# Loginator_1_1.net
KiCad netlist of a schematic drawn in EAGLE
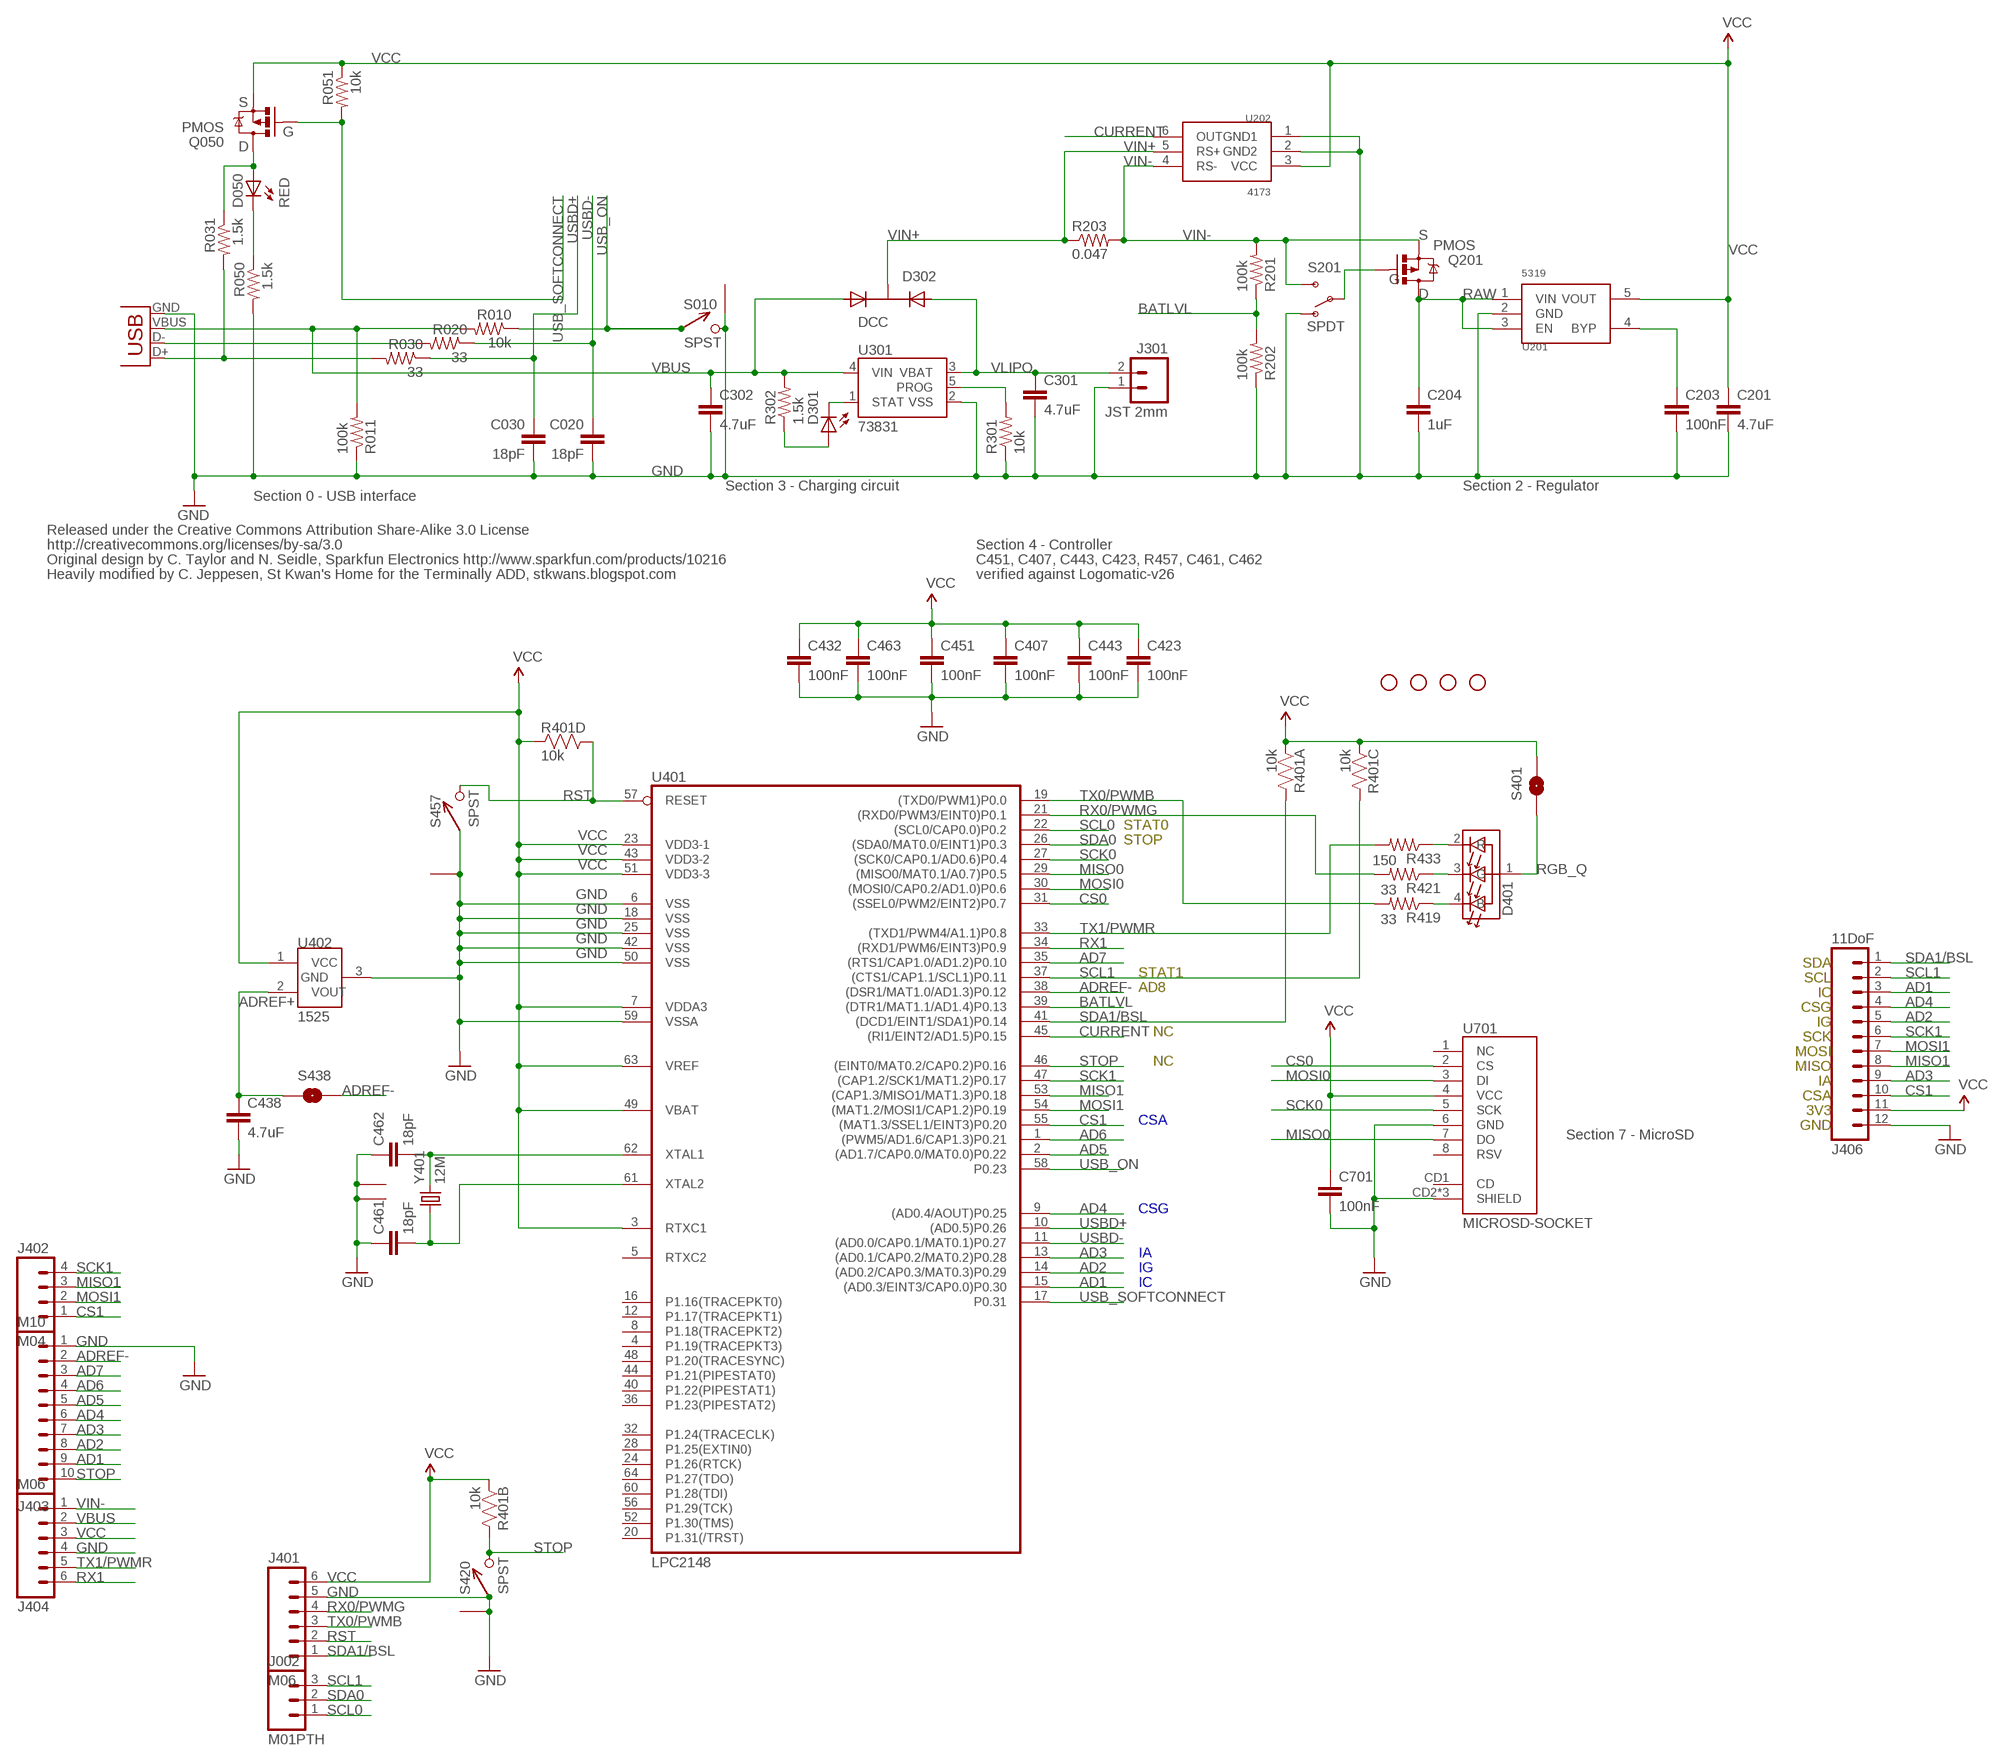
[diagram p0: schematic, sheet 1]

(export (version "E")
  (design (tool "Eeschema 10.0.6"))
  (components
    (comp (ref "C020")
      (value "18pF")
      (footprint "eagle-import:0402-CAP")
      (libsource (lib "eagle-import") (part "CAP0402-CAP"))
    )
    (comp (ref "C030")
      (value "18pF")
      (footprint "eagle-import:0402-CAP")
      (libsource (lib "eagle-import") (part "CAP0402-CAP"))
    )
    (comp (ref "C201")
      (value "4.7uF")
      (footprint "eagle-import:0402-CAP")
      (libsource (lib "eagle-import") (part "CAP0402-CAP"))
    )
    (comp (ref "C203")
      (value "100nF")
      (footprint "eagle-import:0402-CAP")
      (libsource (lib "eagle-import") (part "CAP0402-CAP"))
    )
    (comp (ref "C204")
      (value "1uF")
      (footprint "eagle-import:0402-CAP")
      (libsource (lib "eagle-import") (part "CAP0402-CAP"))
    )
    (comp (ref "C301")
      (value "4.7uF")
      (footprint "eagle-import:0402-CAP")
      (libsource (lib "eagle-import") (part "CAP0402-CAP"))
    )
    (comp (ref "C302")
      (value "4.7uF")
      (footprint "eagle-import:0402-CAP")
      (libsource (lib "eagle-import") (part "CAP0402-CAP"))
    )
    (comp (ref "C407")
      (value "100nF")
      (footprint "eagle-import:0402-CAP")
      (libsource (lib "eagle-import") (part "CAP0402-CAP"))
    )
    (comp (ref "C423")
      (value "100nF")
      (footprint "eagle-import:0402-CAP")
      (libsource (lib "eagle-import") (part "CAP0402-CAP"))
    )
    (comp (ref "C432")
      (value "100nF")
      (footprint "eagle-import:0402-CAP")
      (libsource (lib "eagle-import") (part "CAP0402-CAP"))
    )
    (comp (ref "C438")
      (value "4.7uF")
      (footprint "eagle-import:0402-CAP")
      (libsource (lib "eagle-import") (part "CAP0402-CAP"))
    )
    (comp (ref "C443")
      (value "100nF")
      (footprint "eagle-import:0402-CAP")
      (libsource (lib "eagle-import") (part "CAP0402-CAP"))
    )
    (comp (ref "C451")
      (value "100nF")
      (footprint "eagle-import:0402-CAP")
      (libsource (lib "eagle-import") (part "CAP0402-CAP"))
    )
    (comp (ref "C461")
      (value "18pF")
      (footprint "eagle-import:0402-CAP")
      (libsource (lib "eagle-import") (part "CAP0402-CAP"))
    )
    (comp (ref "C462")
      (value "18pF")
      (footprint "eagle-import:0402-CAP")
      (libsource (lib "eagle-import") (part "CAP0402-CAP"))
    )
    (comp (ref "C463")
      (value "100nF")
      (footprint "eagle-import:0402-CAP")
      (libsource (lib "eagle-import") (part "CAP0402-CAP"))
    )
    (comp (ref "C701")
      (value "100nF")
      (footprint "eagle-import:0402-CAP")
      (libsource (lib "eagle-import") (part "CAP0402-CAP"))
    )
    (comp (ref "D050")
      (value "RED")
      (footprint "eagle-import:LED-0603")
      (libsource (lib "eagle-import") (part "LED0603"))
    )
    (comp (ref "D301")
      (value "RED")
      (footprint "eagle-import:LED-0603")
      (libsource (lib "eagle-import") (part "LED0603"))
    )
    (comp (ref "D302")
      (value "DCC")
      (footprint "eagle-import:SOT-23-3")
      (libsource (lib "eagle-import") (part "PMEG2005CT"))
    )
    (comp (ref "D401")
      (value "HSMF-C118")
      (footprint "eagle-import:HSMF-C118")
      (libsource (lib "eagle-import") (part "HSMF-C118"))
    )
    (comp (ref "J001")
      (value "USBSMD")
      (footprint "eagle-import:USB-MINIB")
      (libsource (lib "eagle-import") (part "USBSMD"))
    )
    (comp (ref "J002")
      (value "M01PTH")
      (footprint "eagle-import:1X03")
      (libsource (lib "eagle-import") (part "M03PTH"))
    )
    (comp (ref "J301")
      (value "JST 2mm")
      (footprint "eagle-import:JST-2-SMD")
      (libsource (lib "eagle-import") (part "M02-JST-2MM-SMT"))
    )
    (comp (ref "J401")
      (value "M06")
      (footprint "eagle-import:1X06")
      (libsource (lib "eagle-import") (part "M06SIP"))
    )
    (comp (ref "J402")
      (value "M04")
      (footprint "eagle-import:1X04")
      (libsource (lib "eagle-import") (part "M04PTH"))
    )
    (comp (ref "J403")
      (value "M10")
      (footprint "eagle-import:1X10")
      (libsource (lib "eagle-import") (part "M10{dblquote}"))
    )
    (comp (ref "J404")
      (value "M06")
      (footprint "eagle-import:1X06")
      (libsource (lib "eagle-import") (part "M06SIP"))
    )
    (comp (ref "J406")
      (value "11DoF")
      (footprint "eagle-import:1X12")
      (libsource (lib "eagle-import") (part "M12PTH"))
    )
    (comp (ref "JP1")
      (value "STAND-OFF")
      (footprint "eagle-import:STAND-OFF")
      (libsource (lib "eagle-import") (part "STAND-OFF"))
    )
    (comp (ref "JP2")
      (value "STAND-OFF")
      (footprint "eagle-import:STAND-OFF")
      (libsource (lib "eagle-import") (part "STAND-OFF"))
    )
    (comp (ref "JP3")
      (value "STAND-OFF")
      (footprint "eagle-import:STAND-OFF")
      (libsource (lib "eagle-import") (part "STAND-OFF"))
    )
    (comp (ref "JP4")
      (value "STAND-OFF")
      (footprint "eagle-import:STAND-OFF")
      (libsource (lib "eagle-import") (part "STAND-OFF"))
    )
    (comp (ref "Q050")
      (value "PMOS")
      (footprint "eagle-import:SOT23-3")
      (libsource (lib "eagle-import") (part "MOSFET-PCHANNELSMD"))
    )
    (comp (ref "Q201")
      (value "PMOS")
      (footprint "eagle-import:SOT23-3")
      (libsource (lib "eagle-import") (part "MOSFET-PCHANNELSMD"))
    )
    (comp (ref "R010")
      (value "10k")
      (footprint "eagle-import:0402-RES")
      (libsource (lib "eagle-import") (part "RESISTOR0402-RES"))
    )
    (comp (ref "R011")
      (value "100k")
      (footprint "eagle-import:0402-RES")
      (libsource (lib "eagle-import") (part "RESISTOR0402-RES"))
    )
    (comp (ref "R020")
      (value "33")
      (footprint "eagle-import:0402-RES")
      (libsource (lib "eagle-import") (part "RESISTOR0402-RES"))
    )
    (comp (ref "R030")
      (value "33")
      (footprint "eagle-import:0402-RES")
      (libsource (lib "eagle-import") (part "RESISTOR0402-RES"))
    )
    (comp (ref "R031")
      (value "1.5k")
      (footprint "eagle-import:0402-RES")
      (libsource (lib "eagle-import") (part "RESISTOR0402-RES"))
    )
    (comp (ref "R050")
      (value "1.5k")
      (footprint "eagle-import:0402-RES")
      (libsource (lib "eagle-import") (part "RESISTOR0402-RES"))
    )
    (comp (ref "R051")
      (value "10k")
      (footprint "eagle-import:0402-RES")
      (libsource (lib "eagle-import") (part "RESISTOR0402-RES"))
    )
    (comp (ref "R201")
      (value "100k")
      (footprint "eagle-import:0402-RES")
      (libsource (lib "eagle-import") (part "RESISTOR0402-RES"))
    )
    (comp (ref "R202")
      (value "100k")
      (footprint "eagle-import:0402-RES")
      (libsource (lib "eagle-import") (part "RESISTOR0402-RES"))
    )
    (comp (ref "R203")
      (value "0.047")
      (footprint "eagle-import:0402-RES")
      (libsource (lib "eagle-import") (part "RESISTOR0402-RES"))
    )
    (comp (ref "R301")
      (value "10k")
      (footprint "eagle-import:0402-RES")
      (libsource (lib "eagle-import") (part "RESISTOR0402-RES"))
    )
    (comp (ref "R302")
      (value "1.5k")
      (footprint "eagle-import:0402-RES")
      (libsource (lib "eagle-import") (part "RESISTOR0402-RES"))
    )
    (comp (ref "R401")
      (value "10k")
      (footprint "eagle-import:CRA04")
      (libsource (lib "eagle-import") (part "RP404"))
    )
    (comp (ref "R419")
      (value "33")
      (footprint "eagle-import:0402-RES")
      (libsource (lib "eagle-import") (part "RESISTOR0402-RES"))
    )
    (comp (ref "R421")
      (value "33")
      (footprint "eagle-import:0402-RES")
      (libsource (lib "eagle-import") (part "RESISTOR0402-RES"))
    )
    (comp (ref "R433")
      (value "150")
      (footprint "eagle-import:0402-RES")
      (libsource (lib "eagle-import") (part "RESISTOR0402-RES"))
    )
    (comp (ref "S010")
      (value "SPST")
      (footprint "eagle-import:B3U-1100P")
      (libsource (lib "eagle-import") (part "B3U-1100P"))
    )
    (comp (ref "S201")
      (value "SPDT")
      (footprint "eagle-import:AYZ0202")
      (libsource (lib "eagle-import") (part "SWITCH-SPSTSMD"))
    )
    (comp (ref "S401")
      (value "SOLDERJUMPERNO")
      (footprint "eagle-import:SJ_2S-NO")
      (libsource (lib "eagle-import") (part "SOLDERJUMPERNO"))
    )
    (comp (ref "S420")
      (value "SPST")
      (footprint "eagle-import:B3U-1100P")
      (libsource (lib "eagle-import") (part "B3U-1100P"))
    )
    (comp (ref "S438")
      (value "SOLDERJUMPERNO")
      (footprint "eagle-import:SJ_2S-NO")
      (libsource (lib "eagle-import") (part "SOLDERJUMPERNO"))
    )
    (comp (ref "S457")
      (value "SPST")
      (footprint "eagle-import:B3U-1100P")
      (libsource (lib "eagle-import") (part "B3U-1100P"))
    )
    (comp (ref "U201")
      (value "5319")
      (footprint "eagle-import:SOT-23-5")
      (libsource (lib "eagle-import") (part "MIC5319D5"))
    )
    (comp (ref "U202")
      (value "4173")
      (footprint "eagle-import:SOT-23-6")
      (libsource (lib "eagle-import") (part "MAX4173"))
    )
    (comp (ref "U301")
      (value "73831")
      (footprint "eagle-import:SOT23-5")
      (libsource (lib "eagle-import") (part "MCP73831"))
    )
    (comp (ref "U401")
      (value "LPC2148")
      (footprint "eagle-import:SQFP-S-10X10-64")
      (libsource (lib "eagle-import") (part "LPC213X"))
    )
    (comp (ref "U402")
      (value "1525")
      (footprint "eagle-import:SOT-23-3")
      (libsource (lib "eagle-import") (part "MCP1525"))
    )
    (comp (ref "U701")
      (value "MICROSD-SOCKET")
      (footprint "eagle-import:MICROSD-SOCKET-PP")
      (libsource (lib "eagle-import") (part "MICROSD-SOCKET"))
    )
    (comp (ref "Y401")
      (value "12M")
      (footprint "eagle-import:CRYSTAL_SMD")
      (libsource (lib "eagle-import") (part "TSX-3225"))
    )
  )
  (nets
    (net (code "1") (name "/AD1") (class "Default")
      (node (ref "J403") (pin "9") (pinfunction "9_9") (pintype "passive"))
      (node (ref "J406") (pin "3") (pinfunction "3_3") (pintype "passive"))
      (node (ref "U401") (pin "15") (pinfunction "(AD0.3/EINT3/CAP0.0)P0.30_15") (pintype "bidirectional"))
    )
    (net (code "2") (name "/AD2") (class "Default")
      (node (ref "J403") (pin "8") (pinfunction "8_8") (pintype "passive"))
      (node (ref "J406") (pin "5") (pinfunction "5_5") (pintype "passive"))
      (node (ref "U401") (pin "14") (pinfunction "(AD0.2/CAP0.3/MAT0.3)P0.29_14") (pintype "bidirectional"))
    )
    (net (code "3") (name "/AD3") (class "Default")
      (node (ref "J403") (pin "7") (pinfunction "7_7") (pintype "passive"))
      (node (ref "J406") (pin "9") (pinfunction "9_9") (pintype "passive"))
      (node (ref "U401") (pin "13") (pinfunction "(AD0.1/CAP0.2/MAT0.2)P0.28_13") (pintype "bidirectional"))
    )
    (net (code "4") (name "/AD4") (class "Default")
      (node (ref "J403") (pin "6") (pinfunction "6_6") (pintype "passive"))
      (node (ref "J406") (pin "4") (pinfunction "4_4") (pintype "passive"))
      (node (ref "U401") (pin "9") (pinfunction "(AD0.4/AOUT)P0.25_9") (pintype "bidirectional"))
    )
    (net (code "5") (name "/AD5") (class "Default")
      (node (ref "J403") (pin "5") (pinfunction "5_5") (pintype "passive"))
      (node (ref "U401") (pin "2") (pinfunction "(AD1.7/CAP0.0/MAT0.0)P0.22_2") (pintype "bidirectional"))
    )
    (net (code "6") (name "/AD6") (class "Default")
      (node (ref "J403") (pin "4") (pinfunction "4_4") (pintype "passive"))
      (node (ref "U401") (pin "1") (pinfunction "(PWM5/AD1.6/CAP1.3)P0.21_1") (pintype "bidirectional"))
    )
    (net (code "7") (name "/AD7") (class "Default")
      (node (ref "J403") (pin "3") (pinfunction "3_3") (pintype "passive"))
      (node (ref "U401") (pin "35") (pinfunction "(RTS1/CAP1.0/AD1.2)P0.10_35") (pintype "bidirectional"))
    )
    (net (code "8") (name "/ADREF+") (class "Default")
      (node (ref "C438") (pin "1") (pinfunction "1_1") (pintype "passive"))
      (node (ref "S438") (pin "1") (pinfunction "1_1") (pintype "passive"))
      (node (ref "U402") (pin "2") (pinfunction "VOUT_2") (pintype "bidirectional"))
    )
    (net (code "9") (name "/ADREF-") (class "Default")
      (node (ref "J403") (pin "2") (pinfunction "2_2") (pintype "passive"))
      (node (ref "S438") (pin "2") (pinfunction "2_2") (pintype "passive"))
      (node (ref "U401") (pin "38") (pinfunction "(DSR1/MAT1.0/AD1.3)P0.12_38") (pintype "bidirectional"))
    )
    (net (code "10") (name "/BATLVL") (class "Default")
      (node (ref "R201") (pin "1") (pinfunction "1_1") (pintype "passive"))
      (node (ref "R202") (pin "2") (pinfunction "2_2") (pintype "passive"))
      (node (ref "U401") (pin "39") (pinfunction "(DTR1/MAT1.1/AD1.4)P0.13_39") (pintype "bidirectional"))
    )
    (net (code "11") (name "/CS0") (class "Default")
      (node (ref "U401") (pin "31") (pinfunction "(SSEL0/PWM2/EINT2)P0.7_31") (pintype "bidirectional"))
      (node (ref "U701") (pin "2") (pinfunction "CS_2") (pintype "bidirectional"))
    )
    (net (code "12") (name "/CS1") (class "Default")
      (node (ref "J402") (pin "1") (pinfunction "1_1") (pintype "passive"))
      (node (ref "J406") (pin "10") (pinfunction "10_10") (pintype "passive"))
      (node (ref "U401") (pin "55") (pinfunction "(MAT1.3/SSEL1/EINT3)P0.20_55") (pintype "bidirectional"))
    )
    (net (code "13") (name "/CURRENT") (class "Default")
      (node (ref "U202") (pin "6") (pinfunction "OUT_6") (pintype "bidirectional"))
      (node (ref "U401") (pin "45") (pinfunction "(RI1/EINT2/AD1.5)P0.15_45") (pintype "bidirectional"))
    )
    (net (code "14") (name "/MISO0") (class "Default")
      (node (ref "U401") (pin "29") (pinfunction "(MISO0/MAT0.1/A0.7)P0.5_29") (pintype "bidirectional"))
      (node (ref "U701") (pin "7") (pinfunction "DO_7") (pintype "bidirectional"))
    )
    (net (code "15") (name "/MISO1") (class "Default")
      (node (ref "J402") (pin "3") (pinfunction "3_3") (pintype "passive"))
      (node (ref "J406") (pin "8") (pinfunction "8_8") (pintype "passive"))
      (node (ref "U401") (pin "53") (pinfunction "(CAP1.3/MISO1/MAT1.3)P0.18_53") (pintype "bidirectional"))
    )
    (net (code "16") (name "/MOSI0") (class "Default")
      (node (ref "U401") (pin "30") (pinfunction "(MOSI0/CAP0.2/AD1.0)P0.6_30") (pintype "bidirectional"))
      (node (ref "U701") (pin "3") (pinfunction "DI_3") (pintype "bidirectional"))
    )
    (net (code "17") (name "/MOSI1") (class "Default")
      (node (ref "J402") (pin "2") (pinfunction "2_2") (pintype "passive"))
      (node (ref "J406") (pin "7") (pinfunction "7_7") (pintype "passive"))
      (node (ref "U401") (pin "54") (pinfunction "(MAT1.2/MOSI1/CAP1.2)P0.19_54") (pintype "bidirectional"))
    )
    (net (code "18") (name "/RAW") (class "Default")
      (node (ref "C204") (pin "1") (pinfunction "1_1") (pintype "passive"))
      (node (ref "Q201") (pin "3") (pinfunction "D_3") (pintype "passive"))
      (node (ref "U201") (pin "1") (pinfunction "VIN_1") (pintype "bidirectional"))
      (node (ref "U201") (pin "3") (pinfunction "EN_3") (pintype "bidirectional"))
    )
    (net (code "19") (name "/RGB_Q") (class "Default")
      (node (ref "D401") (pin "1") (pinfunction "A_1") (pintype "passive"))
      (node (ref "S401") (pin "1") (pinfunction "1_1") (pintype "passive"))
    )
    (net (code "20") (name "/RST") (class "Default")
      (node (ref "J401") (pin "2") (pinfunction "2_2") (pintype "passive"))
      (node (ref "R401") (pin "5") (pinfunction "2_5") (pintype "passive"))
      (node (ref "S457") (pin "P$2") (pinfunction "2_P$2") (pintype "bidirectional"))
      (node (ref "U401") (pin "57") (pinfunction "RESET_57") (pintype "input"))
    )
    (net (code "21") (name "/RX0{slash}PWMG") (class "Default")
      (node (ref "J401") (pin "4") (pinfunction "4_4") (pintype "passive"))
      (node (ref "R421") (pin "2") (pinfunction "2_2") (pintype "passive"))
      (node (ref "U401") (pin "21") (pinfunction "(RXD0/PWM3/EINT0)P0.1_21") (pintype "bidirectional"))
    )
    (net (code "22") (name "/RX1") (class "Default")
      (node (ref "J404") (pin "6") (pinfunction "6_6") (pintype "passive"))
      (node (ref "U401") (pin "34") (pinfunction "(RXD1/PWM6/EINT3)P0.9_34") (pintype "bidirectional"))
    )
    (net (code "23") (name "/SCK0") (class "Default")
      (node (ref "U401") (pin "27") (pinfunction "(SCK0/CAP0.1/AD0.6)P0.4_27") (pintype "bidirectional"))
      (node (ref "U701") (pin "5") (pinfunction "SCK_5") (pintype "bidirectional"))
    )
    (net (code "24") (name "/SCK1") (class "Default")
      (node (ref "J402") (pin "4") (pinfunction "4_4") (pintype "passive"))
      (node (ref "J406") (pin "6") (pinfunction "6_6") (pintype "passive"))
      (node (ref "U401") (pin "47") (pinfunction "(CAP1.2/SCK1/MAT1.2)P0.17_47") (pintype "bidirectional"))
    )
    (net (code "25") (name "/SCL0") (class "Default")
      (node (ref "J002") (pin "1") (pinfunction "1_1") (pintype "passive"))
      (node (ref "U401") (pin "22") (pinfunction "(SCL0/CAP0.0)P0.2_22") (pintype "bidirectional"))
    )
    (net (code "26") (name "/SCL1") (class "Default")
      (node (ref "J002") (pin "3") (pinfunction "3_3") (pintype "passive"))
      (node (ref "J406") (pin "2") (pinfunction "2_2") (pintype "passive"))
      (node (ref "R401") (pin "6") (pinfunction "2_6") (pintype "passive"))
      (node (ref "U401") (pin "37") (pinfunction "(CTS1/CAP1.1/SCL1)P0.11_37") (pintype "bidirectional"))
    )
    (net (code "27") (name "/SDA0") (class "Default")
      (node (ref "J002") (pin "2") (pinfunction "2_2") (pintype "passive"))
      (node (ref "U401") (pin "26") (pinfunction "(SDA0/MAT0.0/EINT1)P0.3_26") (pintype "bidirectional"))
    )
    (net (code "28") (name "/SDA1{slash}BSL") (class "Default")
      (node (ref "J401") (pin "1") (pinfunction "1_1") (pintype "passive"))
      (node (ref "J406") (pin "1") (pinfunction "1_1") (pintype "passive"))
      (node (ref "R401") (pin "8") (pinfunction "2_8") (pintype "passive"))
      (node (ref "U401") (pin "41") (pinfunction "(DCD1/EINT1/SDA1)P0.14_41") (pintype "bidirectional"))
    )
    (net (code "29") (name "/STOP") (class "Default")
      (node (ref "J403") (pin "10") (pinfunction "10_10") (pintype "passive"))
      (node (ref "R401") (pin "7") (pinfunction "2_7") (pintype "passive"))
      (node (ref "S420") (pin "P$2") (pinfunction "2_P$2") (pintype "bidirectional"))
      (node (ref "U401") (pin "46") (pinfunction "(EINT0/MAT0.2/CAP0.2)P0.16_46") (pintype "bidirectional"))
    )
    (net (code "30") (name "/TX0{slash}PWMB") (class "Default")
      (node (ref "J401") (pin "3") (pinfunction "3_3") (pintype "passive"))
      (node (ref "R419") (pin "2") (pinfunction "2_2") (pintype "passive"))
      (node (ref "U401") (pin "19") (pinfunction "(TXD0/PWM1)P0.0_19") (pintype "bidirectional"))
    )
    (net (code "31") (name "/TX1{slash}PWMR") (class "Default")
      (node (ref "J404") (pin "5") (pinfunction "5_5") (pintype "passive"))
      (node (ref "R433") (pin "2") (pinfunction "2_2") (pintype "passive"))
      (node (ref "U401") (pin "33") (pinfunction "(TXD1/PWM4/A1.1)P0.8_33") (pintype "bidirectional"))
    )
    (net (code "32") (name "/USBD+") (class "Default")
      (node (ref "C030") (pin "1") (pinfunction "1_1") (pintype "passive"))
      (node (ref "R030") (pin "1") (pinfunction "1_1") (pintype "passive"))
      (node (ref "U401") (pin "10") (pinfunction "(AD0.5)P0.26_10") (pintype "bidirectional"))
    )
    (net (code "33") (name "/USBD-") (class "Default")
      (node (ref "C020") (pin "1") (pinfunction "1_1") (pintype "passive"))
      (node (ref "R020") (pin "1") (pinfunction "1_1") (pintype "passive"))
      (node (ref "U401") (pin "11") (pinfunction "(AD0.0/CAP0.1/MAT0.1)P0.27_11") (pintype "bidirectional"))
    )
    (net (code "34") (name "/USB_ON") (class "Default")
      (node (ref "R010") (pin "1") (pinfunction "1_1") (pintype "passive"))
      (node (ref "S010") (pin "P$1") (pinfunction "1_P$1") (pintype "bidirectional"))
      (node (ref "U401") (pin "58") (pinfunction "P0.23_58") (pintype "bidirectional"))
    )
    (net (code "35") (name "/USB_SOFTCONNECT") (class "Default")
      (node (ref "Q050") (pin "1") (pinfunction "G_1") (pintype "passive"))
      (node (ref "R051") (pin "2") (pinfunction "2_2") (pintype "passive"))
      (node (ref "U401") (pin "17") (pinfunction "P0.31_17") (pintype "output"))
    )
    (net (code "36") (name "/VBUS") (class "Default")
      (node (ref "C302") (pin "1") (pinfunction "1_1") (pintype "passive"))
      (node (ref "D302") (pin "1") (pinfunction "A1_1") (pintype "passive"))
      (node (ref "J001") (pin "VBUS") (pinfunction "VBUS_VBUS") (pintype "bidirectional"))
      (node (ref "J404") (pin "2") (pinfunction "2_2") (pintype "passive"))
      (node (ref "R010") (pin "2") (pinfunction "2_2") (pintype "passive"))
      (node (ref "R011") (pin "2") (pinfunction "2_2") (pintype "passive"))
      (node (ref "R302") (pin "2") (pinfunction "2_2") (pintype "passive"))
      (node (ref "U301") (pin "4") (pinfunction "VIN_4") (pintype "power_in"))
    )
    (net (code "37") (name "/VIN+") (class "Default")
      (node (ref "D302") (pin "3") (pinfunction "K_3") (pintype "passive"))
      (node (ref "R203") (pin "1") (pinfunction "1_1") (pintype "passive"))
      (node (ref "U202") (pin "5") (pinfunction "RS+_5") (pintype "bidirectional"))
    )
    (net (code "38") (name "/VIN-") (class "Default")
      (node (ref "J404") (pin "1") (pinfunction "1_1") (pintype "passive"))
      (node (ref "Q201") (pin "2") (pinfunction "S_2") (pintype "passive"))
      (node (ref "R201") (pin "2") (pinfunction "2_2") (pintype "passive"))
      (node (ref "R203") (pin "2") (pinfunction "2_2") (pintype "passive"))
      (node (ref "S201") (pin "3") (pinfunction "S_3") (pintype "passive"))
      (node (ref "U202") (pin "4") (pinfunction "RS-_4") (pintype "bidirectional"))
    )
    (net (code "39") (name "/VLIPO") (class "Default")
      (node (ref "C301") (pin "1") (pinfunction "1_1") (pintype "passive"))
      (node (ref "D302") (pin "2") (pinfunction "A2_2") (pintype "passive"))
      (node (ref "J301") (pin "2") (pinfunction "2_2") (pintype "passive"))
      (node (ref "U301") (pin "3") (pinfunction "VBAT_3") (pintype "power_in"))
    )
    (net (code "40") (name "GND") (class "Default")
      (node (ref "C020") (pin "2") (pinfunction "2_2") (pintype "passive"))
      (node (ref "C030") (pin "2") (pinfunction "2_2") (pintype "passive"))
      (node (ref "C201") (pin "2") (pinfunction "2_2") (pintype "passive"))
      (node (ref "C203") (pin "2") (pinfunction "2_2") (pintype "passive"))
      (node (ref "C204") (pin "2") (pinfunction "2_2") (pintype "passive"))
      (node (ref "C301") (pin "2") (pinfunction "2_2") (pintype "passive"))
      (node (ref "C302") (pin "2") (pinfunction "2_2") (pintype "passive"))
      (node (ref "C407") (pin "2") (pinfunction "2_2") (pintype "passive"))
      (node (ref "C423") (pin "2") (pinfunction "2_2") (pintype "passive"))
      (node (ref "C432") (pin "2") (pinfunction "2_2") (pintype "passive"))
      (node (ref "C438") (pin "2") (pinfunction "2_2") (pintype "passive"))
      (node (ref "C443") (pin "2") (pinfunction "2_2") (pintype "passive"))
      (node (ref "C451") (pin "2") (pinfunction "2_2") (pintype "passive"))
      (node (ref "C461") (pin "1") (pinfunction "1_1") (pintype "passive"))
      (node (ref "C462") (pin "1") (pinfunction "1_1") (pintype "passive"))
      (node (ref "C463") (pin "2") (pinfunction "2_2") (pintype "passive"))
      (node (ref "C701") (pin "2") (pinfunction "2_2") (pintype "passive"))
      (node (ref "J001") (pin "GND") (pinfunction "GND_GND") (pintype "bidirectional"))
      (node (ref "J301") (pin "1") (pinfunction "1_1") (pintype "passive"))
      (node (ref "J401") (pin "5") (pinfunction "5_5") (pintype "passive"))
      (node (ref "J403") (pin "1") (pinfunction "1_1") (pintype "passive"))
      (node (ref "J404") (pin "4") (pinfunction "4_4") (pintype "passive"))
      (node (ref "J406") (pin "12") (pinfunction "12_12") (pintype "passive"))
      (node (ref "R011") (pin "1") (pinfunction "1_1") (pintype "passive"))
      (node (ref "R050") (pin "2") (pinfunction "2_2") (pintype "passive"))
      (node (ref "R202") (pin "1") (pinfunction "1_1") (pintype "passive"))
      (node (ref "R301") (pin "1") (pinfunction "1_1") (pintype "passive"))
      (node (ref "S010") (pin "P$2") (pinfunction "2_P$2") (pintype "bidirectional"))
      (node (ref "S010") (pin "P$3") (pinfunction "1_P$3") (pintype "bidirectional"))
      (node (ref "S201") (pin "1") (pinfunction "O_1") (pintype "passive"))
      (node (ref "S420") (pin "P$1") (pinfunction "1_P$1") (pintype "bidirectional"))
      (node (ref "S420") (pin "P$3") (pinfunction "1_P$3") (pintype "bidirectional"))
      (node (ref "S457") (pin "P$1") (pinfunction "1_P$1") (pintype "bidirectional"))
      (node (ref "S457") (pin "P$3") (pinfunction "1_P$3") (pintype "bidirectional"))
      (node (ref "U201") (pin "2") (pinfunction "GND_2") (pintype "bidirectional"))
      (node (ref "U202") (pin "1") (pinfunction "GND1_1") (pintype "bidirectional"))
      (node (ref "U202") (pin "2") (pinfunction "GND2_2") (pintype "bidirectional"))
      (node (ref "U301") (pin "2") (pinfunction "VSS_2") (pintype "power_in"))
      (node (ref "U401") (pin "18") (pinfunction "VSS_18") (pintype "power_in"))
      (node (ref "U401") (pin "25") (pinfunction "VSS_25") (pintype "power_in"))
      (node (ref "U401") (pin "42") (pinfunction "VSS_42") (pintype "power_in"))
      (node (ref "U401") (pin "50") (pinfunction "VSS_50") (pintype "power_in"))
      (node (ref "U401") (pin "59") (pinfunction "VSSA_59") (pintype "power_in"))
      (node (ref "U401") (pin "6") (pinfunction "VSS_6") (pintype "power_in"))
      (node (ref "U402") (pin "3") (pinfunction "GND_3") (pintype "bidirectional"))
      (node (ref "U701") (pin "6") (pinfunction "GND_6") (pintype "bidirectional"))
      (node (ref "U701") (pin "CD2") (pinfunction "SHIELD_CD2") (pintype "bidirectional"))
      (node (ref "U701") (pin "GND1") (pinfunction "SHIELD_GND1") (pintype "bidirectional"))
      (node (ref "U701") (pin "GND3") (pinfunction "SHIELD_GND3") (pintype "bidirectional"))
      (node (ref "Y401") (pin "2") (pinfunction "1_2") (pintype "bidirectional"))
      (node (ref "Y401") (pin "4") (pinfunction "1_4") (pintype "bidirectional"))
    )
    (net (code "41") (name "Net-(D050-PadC)") (class "Default")
      (node (ref "D050") (pin "C") (pinfunction "C_C") (pintype "passive"))
      (node (ref "R050") (pin "1") (pinfunction "1_1") (pintype "passive"))
    )
    (net (code "42") (name "Net-(D301-PadA)") (class "Default")
      (node (ref "D301") (pin "A") (pinfunction "A_A") (pintype "passive"))
      (node (ref "R302") (pin "1") (pinfunction "1_1") (pintype "passive"))
    )
    (net (code "43") (name "Net-(D401-B)") (class "Default")
      (node (ref "D401") (pin "4") (pinfunction "B_4") (pintype "passive"))
      (node (ref "R419") (pin "1") (pinfunction "1_1") (pintype "passive"))
    )
    (net (code "44") (name "Net-(D401-G)") (class "Default")
      (node (ref "D401") (pin "3") (pinfunction "G_3") (pintype "passive"))
      (node (ref "R421") (pin "1") (pinfunction "1_1") (pintype "passive"))
    )
    (net (code "45") (name "Net-(D401-R)") (class "Default")
      (node (ref "D401") (pin "2") (pinfunction "R_2") (pintype "passive"))
      (node (ref "R433") (pin "1") (pinfunction "1_1") (pintype "passive"))
    )
    (net (code "46") (name "Net-(J001-PadD+)") (class "Default")
      (node (ref "J001") (pin "D+") (pinfunction "D+_D+") (pintype "bidirectional"))
      (node (ref "R030") (pin "2") (pinfunction "2_2") (pintype "passive"))
      (node (ref "R031") (pin "2") (pinfunction "2_2") (pintype "passive"))
    )
    (net (code "47") (name "Net-(J001-PadD-)") (class "Default")
      (node (ref "J001") (pin "D-") (pinfunction "D-_D-") (pintype "bidirectional"))
      (node (ref "R020") (pin "2") (pinfunction "2_2") (pintype "passive"))
    )
    (net (code "48") (name "Net-(Q050-D)") (class "Default")
      (node (ref "D050") (pin "A") (pinfunction "A_A") (pintype "passive"))
      (node (ref "Q050") (pin "3") (pinfunction "D_3") (pintype "passive"))
      (node (ref "R031") (pin "1") (pinfunction "1_1") (pintype "passive"))
    )
    (net (code "49") (name "Net-(Q201-G)") (class "Default")
      (node (ref "Q201") (pin "1") (pinfunction "G_1") (pintype "passive"))
      (node (ref "S201") (pin "2") (pinfunction "P_2") (pintype "passive"))
    )
    (net (code "50") (name "Net-(U201-BYP)") (class "Default")
      (node (ref "C203") (pin "1") (pinfunction "1_1") (pintype "passive"))
      (node (ref "U201") (pin "4") (pinfunction "BYP_4") (pintype "bidirectional"))
    )
    (net (code "51") (name "Net-(U301-PROG)") (class "Default")
      (node (ref "R301") (pin "2") (pinfunction "2_2") (pintype "passive"))
      (node (ref "U301") (pin "5") (pinfunction "PROG_5") (pintype "input"))
    )
    (net (code "52") (name "Net-(U301-STAT)") (class "Default")
      (node (ref "D301") (pin "C") (pinfunction "C_C") (pintype "passive"))
      (node (ref "U301") (pin "1") (pinfunction "STAT_1") (pintype "output"))
    )
    (net (code "53") (name "Net-(U401-XTAL1)") (class "Default")
      (node (ref "C462") (pin "2") (pinfunction "2_2") (pintype "passive"))
      (node (ref "U401") (pin "62") (pinfunction "XTAL1_62") (pintype "input"))
      (node (ref "Y401") (pin "3") (pinfunction "2_3") (pintype "passive"))
    )
    (net (code "54") (name "Net-(U401-XTAL2)") (class "Default")
      (node (ref "C461") (pin "2") (pinfunction "2_2") (pintype "passive"))
      (node (ref "U401") (pin "61") (pinfunction "XTAL2_61") (pintype "output"))
      (node (ref "Y401") (pin "1") (pinfunction "1_1") (pintype "passive"))
    )
    (net (code "55") (name "VCC") (class "Default")
      (node (ref "C201") (pin "1") (pinfunction "1_1") (pintype "passive"))
      (node (ref "C407") (pin "1") (pinfunction "1_1") (pintype "passive"))
      (node (ref "C423") (pin "1") (pinfunction "1_1") (pintype "passive"))
      (node (ref "C432") (pin "1") (pinfunction "1_1") (pintype "passive"))
      (node (ref "C443") (pin "1") (pinfunction "1_1") (pintype "passive"))
      (node (ref "C451") (pin "1") (pinfunction "1_1") (pintype "passive"))
      (node (ref "C463") (pin "1") (pinfunction "1_1") (pintype "passive"))
      (node (ref "C701") (pin "1") (pinfunction "1_1") (pintype "passive"))
      (node (ref "J401") (pin "6") (pinfunction "6_6") (pintype "passive"))
      (node (ref "J404") (pin "3") (pinfunction "3_3") (pintype "passive"))
      (node (ref "J406") (pin "11") (pinfunction "11_11") (pintype "passive"))
      (node (ref "Q050") (pin "2") (pinfunction "S_2") (pintype "passive"))
      (node (ref "R051") (pin "1") (pinfunction "1_1") (pintype "passive"))
      (node (ref "R401") (pin "1") (pinfunction "1_1") (pintype "passive"))
      (node (ref "R401") (pin "2") (pinfunction "1_2") (pintype "passive"))
      (node (ref "R401") (pin "3") (pinfunction "1_3") (pintype "passive"))
      (node (ref "R401") (pin "4") (pinfunction "1_4") (pintype "passive"))
      (node (ref "S401") (pin "2") (pinfunction "2_2") (pintype "passive"))
      (node (ref "U201") (pin "5") (pinfunction "VOUT_5") (pintype "bidirectional"))
      (node (ref "U202") (pin "3") (pinfunction "VCC_3") (pintype "bidirectional"))
      (node (ref "U401") (pin "23") (pinfunction "VDD3-1_23") (pintype "power_in"))
      (node (ref "U401") (pin "3") (pinfunction "RTXC1_3") (pintype "input"))
      (node (ref "U401") (pin "43") (pinfunction "VDD3-2_43") (pintype "power_in"))
      (node (ref "U401") (pin "49") (pinfunction "VBAT_49") (pintype "power_in"))
      (node (ref "U401") (pin "51") (pinfunction "VDD3-3_51") (pintype "power_in"))
      (node (ref "U401") (pin "63") (pinfunction "VREF_63") (pintype "input"))
      (node (ref "U401") (pin "7") (pinfunction "VDDA3_7") (pintype "power_in"))
      (node (ref "U402") (pin "1") (pinfunction "VCC_1") (pintype "bidirectional"))
      (node (ref "U701") (pin "4") (pinfunction "VCC_4") (pintype "bidirectional"))
    )
    (net (code "56") (name "unconnected-(U401-P1.16(TRACEPKT0)-Pad16)") (class "Default")
      (node (ref "U401") (pin "16") (pinfunction "P1.16(TRACEPKT0)_16") (pintype "bidirectional"))
    )
    (net (code "57") (name "unconnected-(U401-P1.17(TRACEPKT1)-Pad12)") (class "Default")
      (node (ref "U401") (pin "12") (pinfunction "P1.17(TRACEPKT1)_12") (pintype "bidirectional"))
    )
    (net (code "58") (name "unconnected-(U401-P1.18(TRACEPKT2)-Pad8)") (class "Default")
      (node (ref "U401") (pin "8") (pinfunction "P1.18(TRACEPKT2)_8") (pintype "bidirectional"))
    )
    (net (code "59") (name "unconnected-(U401-P1.19(TRACEPKT3)-Pad4)") (class "Default")
      (node (ref "U401") (pin "4") (pinfunction "P1.19(TRACEPKT3)_4") (pintype "bidirectional"))
    )
    (net (code "60") (name "unconnected-(U401-P1.20(TRACESYNC)-Pad48)") (class "Default")
      (node (ref "U401") (pin "48") (pinfunction "P1.20(TRACESYNC)_48") (pintype "bidirectional"))
    )
    (net (code "61") (name "unconnected-(U401-P1.21(PIPESTAT0)-Pad44)") (class "Default")
      (node (ref "U401") (pin "44") (pinfunction "P1.21(PIPESTAT0)_44") (pintype "bidirectional"))
    )
    (net (code "62") (name "unconnected-(U401-P1.22(PIPESTAT1)-Pad40)") (class "Default")
      (node (ref "U401") (pin "40") (pinfunction "P1.22(PIPESTAT1)_40") (pintype "bidirectional"))
    )
    (net (code "63") (name "unconnected-(U401-P1.23(PIPESTAT2)-Pad36)") (class "Default")
      (node (ref "U401") (pin "36") (pinfunction "P1.23(PIPESTAT2)_36") (pintype "bidirectional"))
    )
    (net (code "64") (name "unconnected-(U401-P1.24(TRACECLK)-Pad32)") (class "Default")
      (node (ref "U401") (pin "32") (pinfunction "P1.24(TRACECLK)_32") (pintype "bidirectional"))
    )
    (net (code "65") (name "unconnected-(U401-P1.25(EXTIN0)-Pad28)") (class "Default")
      (node (ref "U401") (pin "28") (pinfunction "P1.25(EXTIN0)_28") (pintype "bidirectional"))
    )
    (net (code "66") (name "unconnected-(U401-P1.26(RTCK)-Pad24)") (class "Default")
      (node (ref "U401") (pin "24") (pinfunction "P1.26(RTCK)_24") (pintype "bidirectional"))
    )
    (net (code "67") (name "unconnected-(U401-P1.27(TDO)-Pad64)") (class "Default")
      (node (ref "U401") (pin "64") (pinfunction "P1.27(TDO)_64") (pintype "bidirectional"))
    )
    (net (code "68") (name "unconnected-(U401-P1.28(TDI)-Pad60)") (class "Default")
      (node (ref "U401") (pin "60") (pinfunction "P1.28(TDI)_60") (pintype "bidirectional"))
    )
    (net (code "69") (name "unconnected-(U401-P1.29(TCK)-Pad56)") (class "Default")
      (node (ref "U401") (pin "56") (pinfunction "P1.29(TCK)_56") (pintype "bidirectional"))
    )
    (net (code "70") (name "unconnected-(U401-P1.30(TMS)-Pad52)") (class "Default")
      (node (ref "U401") (pin "52") (pinfunction "P1.30(TMS)_52") (pintype "bidirectional"))
    )
    (net (code "71") (name "unconnected-(U401-P1.31({slash}TRST)-Pad20)") (class "Default")
      (node (ref "U401") (pin "20") (pinfunction "P1.31(/TRST)_20") (pintype "bidirectional"))
    )
    (net (code "72") (name "unconnected-(U401-RTXC2-Pad5)") (class "Default")
      (node (ref "U401") (pin "5") (pinfunction "RTXC2_5") (pintype "output"))
    )
    (net (code "73") (name "unconnected-(U701-CD-PadCD1)") (class "Default")
      (node (ref "U701") (pin "CD1") (pinfunction "CD_CD1") (pintype "bidirectional"))
    )
    (net (code "74") (name "unconnected-(U701-NC-Pad1)") (class "Default")
      (node (ref "U701") (pin "1") (pinfunction "NC_1") (pintype "bidirectional"))
    )
    (net (code "75") (name "unconnected-(U701-RSV-Pad8)") (class "Default")
      (node (ref "U701") (pin "8") (pinfunction "RSV_8") (pintype "bidirectional"))
    )
  )
)
